# SensorControl.net
KiCad netlist of a schematic drawn in Altium Designer
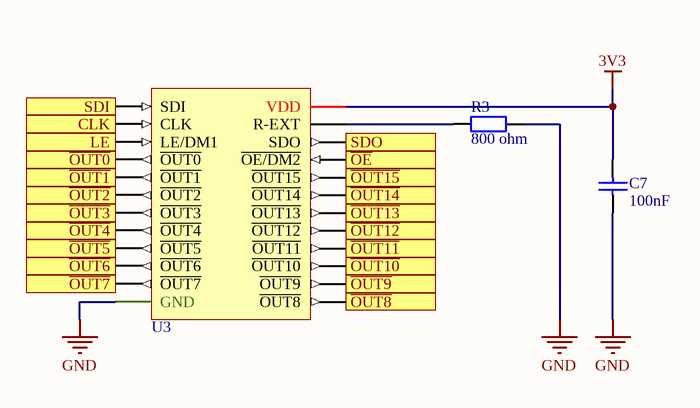
[diagram p0: SensorControl.SchDoc]

(export (version "E")
  (design (tool "Eeschema 10.0.6"))
  (components
    (comp (ref "C7")
      (value "100nF")
      (footprint "FP_0805_CAP_085")
      (description "Capacitor")
      (fields (field (name "TOLERANCE") "+80%/-20%") (field (name "VOLTAGE") "25V"))
      (libsource (lib "hallglib") (part "CAP 100nF"))
    )
    (comp (ref "R3")
      (value "CRCW0805806RFKEA")
      (footprint "0805-W")
      (description "RES, THICK FILM, 806R, 1%, 0.125W, 0805")
      (fields (field (name "RESISTANCE") "800 ohm"))
      (libsource (lib "RobonAUT") (part "CRCW0805806RFKEA"))
    )
    (comp (ref "U3")
      (value "STP16CP05TTR")
      (footprint "24-Pin TSSOP")
      (description "Led Driver, 16 Outputs, Constant Current, 3V-5.5V in, 30MHz switch, 20V/100mA out, TSSOP-24")
      (libsource (lib "RobonAUT") (part "STP16CP05TTR"))
    )
  )
  (nets
    (net (code "1") (name "/CLK") (class "Default")
      (node (ref "U3") (pin "3") (pinfunction "CLK_3") (pintype "input"))
    )
    (net (code "2") (name "/LE") (class "Default")
      (node (ref "U3") (pin "4") (pinfunction "LE/DM1_4") (pintype "input"))
    )
    (net (code "3") (name "/SDI") (class "Default")
      (node (ref "U3") (pin "2") (pinfunction "SDI_2") (pintype "input"))
    )
    (net (code "4") (name "/SDO") (class "Default")
      (node (ref "U3") (pin "22") (pinfunction "SDO_22") (pintype "output"))
    )
    (net (code "5") (name "/~{OE}") (class "Default")
      (node (ref "U3") (pin "21") (pinfunction "~{OE/DM2}_21") (pintype "input"))
    )
    (net (code "6") (name "/~{OUT0}") (class "Default")
      (node (ref "U3") (pin "5") (pinfunction "~{OUT0}_5") (pintype "output"))
    )
    (net (code "7") (name "/~{OUT1}") (class "Default")
      (node (ref "U3") (pin "6") (pinfunction "~{OUT1}_6") (pintype "output"))
    )
    (net (code "8") (name "/~{OUT2}") (class "Default")
      (node (ref "U3") (pin "7") (pinfunction "~{OUT2}_7") (pintype "output"))
    )
    (net (code "9") (name "/~{OUT3}") (class "Default")
      (node (ref "U3") (pin "8") (pinfunction "~{OUT3}_8") (pintype "output"))
    )
    (net (code "10") (name "/~{OUT4}") (class "Default")
      (node (ref "U3") (pin "9") (pinfunction "~{OUT4}_9") (pintype "output"))
    )
    (net (code "11") (name "/~{OUT5}") (class "Default")
      (node (ref "U3") (pin "10") (pinfunction "~{OUT5}_10") (pintype "output"))
    )
    (net (code "12") (name "/~{OUT6}") (class "Default")
      (node (ref "U3") (pin "11") (pinfunction "~{OUT6}_11") (pintype "output"))
    )
    (net (code "13") (name "/~{OUT7}") (class "Default")
      (node (ref "U3") (pin "12") (pinfunction "~{OUT7}_12") (pintype "output"))
    )
    (net (code "14") (name "/~{OUT8}") (class "Default")
      (node (ref "U3") (pin "13") (pinfunction "~{OUT8}_13") (pintype "output"))
    )
    (net (code "15") (name "/~{OUT9}") (class "Default")
      (node (ref "U3") (pin "14") (pinfunction "~{OUT9}_14") (pintype "output"))
    )
    (net (code "16") (name "/~{OUT10}") (class "Default")
      (node (ref "U3") (pin "15") (pinfunction "~{OUT10}_15") (pintype "output"))
    )
    (net (code "17") (name "/~{OUT11}") (class "Default")
      (node (ref "U3") (pin "16") (pinfunction "~{OUT11}_16") (pintype "output"))
    )
    (net (code "18") (name "/~{OUT12}") (class "Default")
      (node (ref "U3") (pin "17") (pinfunction "~{OUT12}_17") (pintype "output"))
    )
    (net (code "19") (name "/~{OUT13}") (class "Default")
      (node (ref "U3") (pin "18") (pinfunction "~{OUT13}_18") (pintype "output"))
    )
    (net (code "20") (name "/~{OUT14}") (class "Default")
      (node (ref "U3") (pin "19") (pinfunction "~{OUT14}_19") (pintype "output"))
    )
    (net (code "21") (name "/~{OUT15}") (class "Default")
      (node (ref "U3") (pin "20") (pinfunction "~{OUT15}_20") (pintype "output"))
    )
    (net (code "22") (name "3V3") (class "Default")
      (node (ref "C7") (pin "2") (pinfunction "2_2") (pintype "passive"))
      (node (ref "U3") (pin "24") (pinfunction "VDD_24") (pintype "power_in"))
    )
    (net (code "23") (name "GND") (class "Default")
      (node (ref "C7") (pin "1") (pinfunction "1_1") (pintype "passive"))
      (node (ref "R3") (pin "2") (pinfunction "2_2") (pintype "passive"))
      (node (ref "U3") (pin "1") (pinfunction "GND_1") (pintype "power_in"))
    )
    (net (code "24") (name "Net-(U3-R-EXT)") (class "Default")
      (node (ref "R3") (pin "1") (pinfunction "1_1") (pintype "passive"))
      (node (ref "U3") (pin "23") (pinfunction "R-EXT_23") (pintype "passive"))
    )
  )
)
